# LEDS.net
KiCad netlist of a schematic drawn in Altium Designer
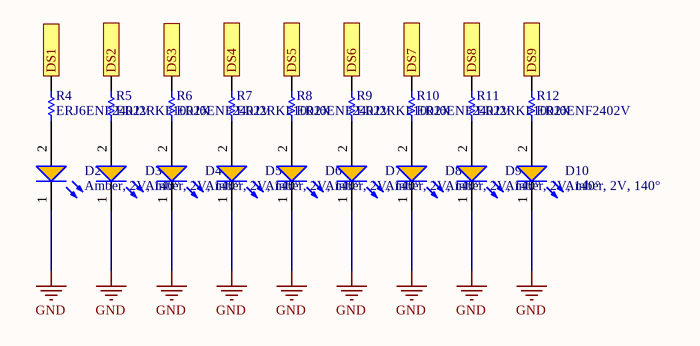
[diagram p0: LEDS.SchDoc]

(export (version "E")
  (design (tool "Eeschema 10.0.6"))
  (components
    (comp (ref "D2")
      (value "Amber, 2V, 140°")
      (footprint "WL-SMCW_0603_150060xx75000")
      (description "WL-SMCW Mono-color Chip LED Waterclear, SMT, size 0603, Amber, 2V, 140°")
      (fields
        (field (name "MANUFACTURER PART NUMBER") "150060AS75000")
        (field (name "MANUFACTURER") "Wurth Elektronik")
      )
      (libsource (lib "150060AS75000_Altium_WL-SMCW_rev24b") (part "150060AS75000"))
    )
    (comp (ref "D3")
      (value "Amber, 2V, 140°")
      (footprint "WL-SMCW_0603_150060xx75000")
      (description "WL-SMCW Mono-color Chip LED Waterclear, SMT, size 0603, Amber, 2V, 140°")
      (fields
        (field (name "MANUFACTURER PART NUMBER") "150060AS75000")
        (field (name "MANUFACTURER") "Wurth Elektronik")
      )
      (libsource (lib "150060AS75000_Altium_WL-SMCW_rev24b") (part "150060AS75000"))
    )
    (comp (ref "D4")
      (value "Amber, 2V, 140°")
      (footprint "WL-SMCW_0603_150060xx75000")
      (description "WL-SMCW Mono-color Chip LED Waterclear, SMT, size 0603, Amber, 2V, 140°")
      (fields
        (field (name "MANUFACTURER PART NUMBER") "150060AS75000")
        (field (name "MANUFACTURER") "Wurth Elektronik")
      )
      (libsource (lib "150060AS75000_Altium_WL-SMCW_rev24b") (part "150060AS75000"))
    )
    (comp (ref "D5")
      (value "Amber, 2V, 140°")
      (footprint "WL-SMCW_0603_150060xx75000")
      (description "WL-SMCW Mono-color Chip LED Waterclear, SMT, size 0603, Amber, 2V, 140°")
      (fields
        (field (name "MANUFACTURER PART NUMBER") "150060AS75000")
        (field (name "MANUFACTURER") "Wurth Elektronik")
      )
      (libsource (lib "150060AS75000_Altium_WL-SMCW_rev24b") (part "150060AS75000"))
    )
    (comp (ref "D6")
      (value "Amber, 2V, 140°")
      (footprint "WL-SMCW_0603_150060xx75000")
      (description "WL-SMCW Mono-color Chip LED Waterclear, SMT, size 0603, Amber, 2V, 140°")
      (fields
        (field (name "MANUFACTURER PART NUMBER") "150060AS75000")
        (field (name "MANUFACTURER") "Wurth Elektronik")
      )
      (libsource (lib "150060AS75000_Altium_WL-SMCW_rev24b") (part "150060AS75000"))
    )
    (comp (ref "D7")
      (value "Amber, 2V, 140°")
      (footprint "WL-SMCW_0603_150060xx75000")
      (description "WL-SMCW Mono-color Chip LED Waterclear, SMT, size 0603, Amber, 2V, 140°")
      (fields
        (field (name "MANUFACTURER PART NUMBER") "150060AS75000")
        (field (name "MANUFACTURER") "Wurth Elektronik")
      )
      (libsource (lib "150060AS75000_Altium_WL-SMCW_rev24b") (part "150060AS75000"))
    )
    (comp (ref "D8")
      (value "Amber, 2V, 140°")
      (footprint "WL-SMCW_0603_150060xx75000")
      (description "WL-SMCW Mono-color Chip LED Waterclear, SMT, size 0603, Amber, 2V, 140°")
      (fields
        (field (name "MANUFACTURER PART NUMBER") "150060AS75000")
        (field (name "MANUFACTURER") "Wurth Elektronik")
      )
      (libsource (lib "150060AS75000_Altium_WL-SMCW_rev24b") (part "150060AS75000"))
    )
    (comp (ref "D9")
      (value "Amber, 2V, 140°")
      (footprint "WL-SMCW_0603_150060xx75000")
      (description "WL-SMCW Mono-color Chip LED Waterclear, SMT, size 0603, Amber, 2V, 140°")
      (fields
        (field (name "MANUFACTURER PART NUMBER") "150060AS75000")
        (field (name "MANUFACTURER") "Wurth Elektronik")
      )
      (libsource (lib "150060AS75000_Altium_WL-SMCW_rev24b") (part "150060AS75000"))
    )
    (comp (ref "D10")
      (value "Amber, 2V, 140°")
      (footprint "WL-SMCW_0603_150060xx75000")
      (description "WL-SMCW Mono-color Chip LED Waterclear, SMT, size 0603, Amber, 2V, 140°")
      (fields
        (field (name "MANUFACTURER PART NUMBER") "150060AS75000")
        (field (name "MANUFACTURER") "Wurth Elektronik")
      )
      (libsource (lib "150060AS75000_Altium_WL-SMCW_rev24b") (part "150060AS75000"))
    )
    (comp (ref "R4")
      (value "ERJ6ENF2402V")
      (footprint "RESC2013X70X40ML20T20")
      (fields (field (name "MANUFACTURER") "Panasonic"))
      (libsource (lib "Altium Content Vault") (part "RES"))
    )
    (comp (ref "R5")
      (value "ERJ2RKF1002X")
      (footprint "RESC1005X40X25LL05T05")
      (description "Chip Resistor, 10 KOhm, +/- 1%, 0.1 W, -55 to 155 degC, 0402 (1005 Metric), RoHS, Tape and Reel")
      (fields (field (name "TOLERANCE") "1%") (field (name "MANUFACTURER") "Panasonic"))
      (libsource (lib "Altium Content Vault") (part "RES-2"))
    )
    (comp (ref "R6")
      (value "ERJ6ENF2402V")
      (footprint "RESC2013X70X40ML20T20")
      (fields (field (name "MANUFACTURER") "Panasonic"))
      (libsource (lib "Altium Content Vault") (part "RES"))
    )
    (comp (ref "R7")
      (value "ERJ2RKF1002X")
      (footprint "RESC1005X40X25LL05T05")
      (description "Chip Resistor, 10 KOhm, +/- 1%, 0.1 W, -55 to 155 degC, 0402 (1005 Metric), RoHS, Tape and Reel")
      (fields (field (name "TOLERANCE") "1%") (field (name "MANUFACTURER") "Panasonic"))
      (libsource (lib "Altium Content Vault") (part "RES-2"))
    )
    (comp (ref "R8")
      (value "ERJ6ENF2402V")
      (footprint "RESC2013X70X40ML20T20")
      (fields (field (name "MANUFACTURER") "Panasonic"))
      (libsource (lib "Altium Content Vault") (part "RES"))
    )
    (comp (ref "R9")
      (value "ERJ2RKF1002X")
      (footprint "RESC1005X40X25LL05T05")
      (description "Chip Resistor, 10 KOhm, +/- 1%, 0.1 W, -55 to 155 degC, 0402 (1005 Metric), RoHS, Tape and Reel")
      (fields (field (name "TOLERANCE") "1%") (field (name "MANUFACTURER") "Panasonic"))
      (libsource (lib "Altium Content Vault") (part "RES-2"))
    )
    (comp (ref "R10")
      (value "ERJ6ENF2402V")
      (footprint "RESC2013X70X40ML20T20")
      (fields (field (name "MANUFACTURER") "Panasonic"))
      (libsource (lib "Altium Content Vault") (part "RES"))
    )
    (comp (ref "R11")
      (value "ERJ2RKF1002X")
      (footprint "RESC1005X40X25LL05T05")
      (description "Chip Resistor, 10 KOhm, +/- 1%, 0.1 W, -55 to 155 degC, 0402 (1005 Metric), RoHS, Tape and Reel")
      (fields (field (name "TOLERANCE") "1%") (field (name "MANUFACTURER") "Panasonic"))
      (libsource (lib "Altium Content Vault") (part "RES-2"))
    )
    (comp (ref "R12")
      (value "ERJ6ENF2402V")
      (footprint "RESC2013X70X40ML20T20")
      (fields (field (name "MANUFACTURER") "Panasonic"))
      (libsource (lib "Altium Content Vault") (part "RES"))
    )
  )
  (nets
    (net (code "1") (name "/DS1") (class "Default")
      (node (ref "R4") (pin "2") (pinfunction "2_2") (pintype "passive"))
    )
    (net (code "2") (name "/DS2") (class "Default")
      (node (ref "R5") (pin "1") (pinfunction "1_1") (pintype "passive"))
    )
    (net (code "3") (name "/DS3") (class "Default")
      (node (ref "R6") (pin "2") (pinfunction "2_2") (pintype "passive"))
    )
    (net (code "4") (name "/DS4") (class "Default")
      (node (ref "R7") (pin "1") (pinfunction "1_1") (pintype "passive"))
    )
    (net (code "5") (name "/DS5") (class "Default")
      (node (ref "R8") (pin "2") (pinfunction "2_2") (pintype "passive"))
    )
    (net (code "6") (name "/DS6") (class "Default")
      (node (ref "R9") (pin "1") (pinfunction "1_1") (pintype "passive"))
    )
    (net (code "7") (name "/DS7") (class "Default")
      (node (ref "R10") (pin "2") (pinfunction "2_2") (pintype "passive"))
    )
    (net (code "8") (name "/DS8") (class "Default")
      (node (ref "R11") (pin "1") (pinfunction "1_1") (pintype "passive"))
    )
    (net (code "9") (name "/DS9") (class "Default")
      (node (ref "R12") (pin "2") (pinfunction "2_2") (pintype "passive"))
    )
    (net (code "10") (name "GND") (class "Default")
      (node (ref "D10") (pin "1") (pinfunction "K_1") (pintype "passive"))
      (node (ref "D2") (pin "1") (pinfunction "K_1") (pintype "passive"))
      (node (ref "D3") (pin "1") (pinfunction "K_1") (pintype "passive"))
      (node (ref "D4") (pin "1") (pinfunction "K_1") (pintype "passive"))
      (node (ref "D5") (pin "1") (pinfunction "K_1") (pintype "passive"))
      (node (ref "D6") (pin "1") (pinfunction "K_1") (pintype "passive"))
      (node (ref "D7") (pin "1") (pinfunction "K_1") (pintype "passive"))
      (node (ref "D8") (pin "1") (pinfunction "K_1") (pintype "passive"))
      (node (ref "D9") (pin "1") (pinfunction "K_1") (pintype "passive"))
    )
    (net (code "11") (name "Net-(D2-A)") (class "Default")
      (node (ref "D2") (pin "2") (pinfunction "A_2") (pintype "passive"))
      (node (ref "R4") (pin "1") (pinfunction "1_1") (pintype "passive"))
    )
    (net (code "12") (name "Net-(D3-A)") (class "Default")
      (node (ref "D3") (pin "2") (pinfunction "A_2") (pintype "passive"))
      (node (ref "R5") (pin "2") (pinfunction "2_2") (pintype "passive"))
    )
    (net (code "13") (name "Net-(D4-A)") (class "Default")
      (node (ref "D4") (pin "2") (pinfunction "A_2") (pintype "passive"))
      (node (ref "R6") (pin "1") (pinfunction "1_1") (pintype "passive"))
    )
    (net (code "14") (name "Net-(D5-A)") (class "Default")
      (node (ref "D5") (pin "2") (pinfunction "A_2") (pintype "passive"))
      (node (ref "R7") (pin "2") (pinfunction "2_2") (pintype "passive"))
    )
    (net (code "15") (name "Net-(D6-A)") (class "Default")
      (node (ref "D6") (pin "2") (pinfunction "A_2") (pintype "passive"))
      (node (ref "R8") (pin "1") (pinfunction "1_1") (pintype "passive"))
    )
    (net (code "16") (name "Net-(D7-A)") (class "Default")
      (node (ref "D7") (pin "2") (pinfunction "A_2") (pintype "passive"))
      (node (ref "R9") (pin "2") (pinfunction "2_2") (pintype "passive"))
    )
    (net (code "17") (name "Net-(D8-A)") (class "Default")
      (node (ref "D8") (pin "2") (pinfunction "A_2") (pintype "passive"))
      (node (ref "R10") (pin "1") (pinfunction "1_1") (pintype "passive"))
    )
    (net (code "18") (name "Net-(D9-A)") (class "Default")
      (node (ref "D9") (pin "2") (pinfunction "A_2") (pintype "passive"))
      (node (ref "R11") (pin "2") (pinfunction "2_2") (pintype "passive"))
    )
    (net (code "19") (name "Net-(D10-A)") (class "Default")
      (node (ref "D10") (pin "2") (pinfunction "A_2") (pintype "passive"))
      (node (ref "R12") (pin "1") (pinfunction "1_1") (pintype "passive"))
    )
  )
)
